# KASLI_CON.net
KiCad netlist of a schematic drawn in Altium Designer
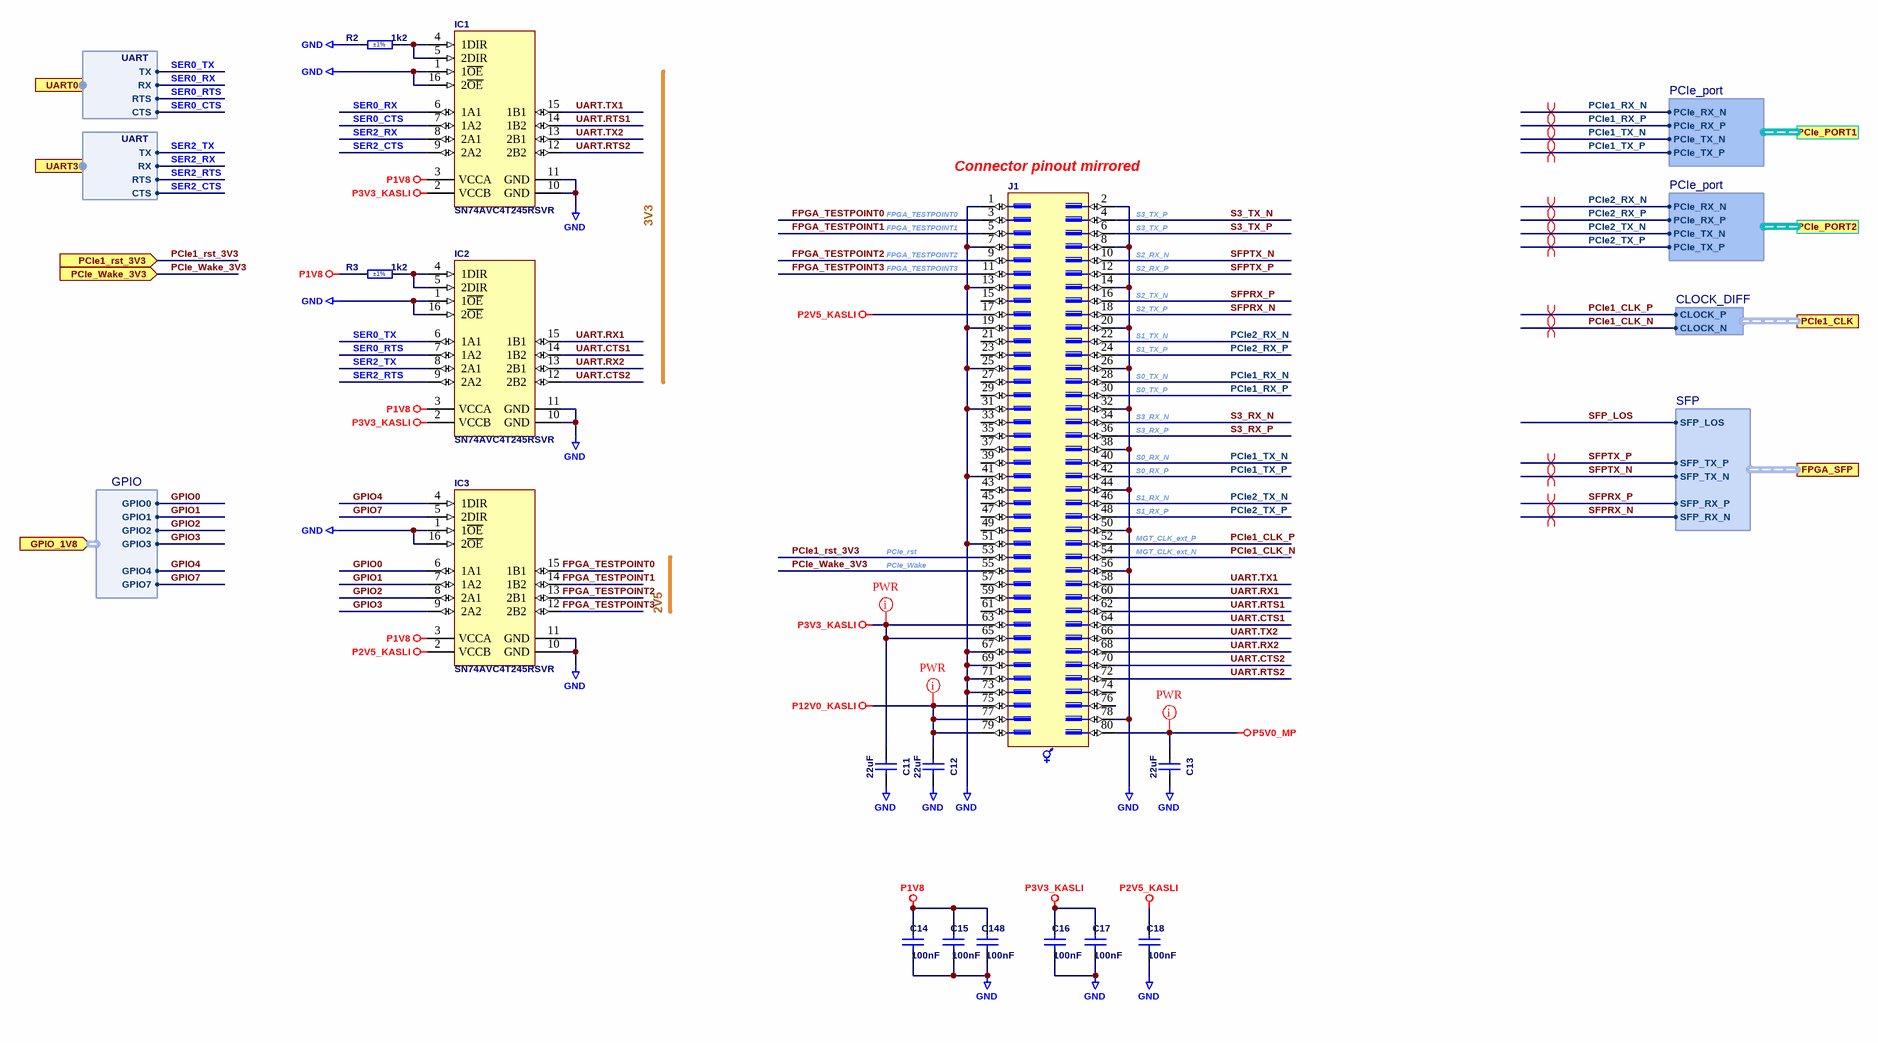
[diagram p0: KASLI_CON.SchDoc]

(export (version "E")
  (design (tool "Eeschema 10.0.6"))
  (components
    (comp (ref "C11")
      (value "22uF")
      (footprint "CAPC2012X135N")
      (description "Non-polarised capacitor")
      (fields
        (field (name "MANUFACTURER PART NUMBER") "CC0805_22UF_16V_10%_X5R")
        (field (name "MANUFACTURER") "GENERIC")
        (field (name "AUTHOR") "CERN DEM JLC")
      )
      (libsource (lib "Capacitors") (part "Capacitor - non polarized"))
    )
    (comp (ref "C12")
      (value "22uF")
      (footprint "CAPC2012X135N")
      (description "Non-polarised capacitor")
      (fields
        (field (name "MANUFACTURER PART NUMBER") "CC0805_22UF_16V_10%_X5R")
        (field (name "MANUFACTURER") "GENERIC")
        (field (name "AUTHOR") "CERN DEM JLC")
      )
      (libsource (lib "Capacitors") (part "Capacitor - non polarized"))
    )
    (comp (ref "C13")
      (value "22uF")
      (footprint "CAPC2012X135N")
      (description "Non-polarised capacitor")
      (fields
        (field (name "MANUFACTURER PART NUMBER") "CC0805_22UF_16V_10%_X5R")
        (field (name "MANUFACTURER") "GENERIC")
        (field (name "AUTHOR") "CERN DEM JLC")
      )
      (libsource (lib "Capacitors") (part "Capacitor - non polarized"))
    )
    (comp (ref "C14")
      (value "100nF")
      (footprint "CAPC1005X55N")
      (description "Non-polarised capacitor")
      (fields
        (field (name "PART NUMBER") "CC0402_100NF_16V_10%_X7R")
        (field (name "VOLTAGE") "16V")
        (field (name "AUTHOR") "CERN DEM JLC")
      )
      (libsource (lib "Capacitors") (part "Capacitor - non polarized"))
    )
    (comp (ref "C15")
      (value "100nF")
      (footprint "CAPC1005X55N")
      (description "Non-polarised capacitor")
      (fields
        (field (name "PART NUMBER") "CC0402_100NF_16V_10%_X7R")
        (field (name "VOLTAGE") "16V")
        (field (name "AUTHOR") "CERN DEM JLC")
      )
      (libsource (lib "Capacitors") (part "Capacitor - non polarized"))
    )
    (comp (ref "C16")
      (value "100nF")
      (footprint "CAPC1005X55N")
      (description "Non-polarised capacitor")
      (fields
        (field (name "PART NUMBER") "CC0402_100NF_16V_10%_X7R")
        (field (name "VOLTAGE") "16V")
        (field (name "AUTHOR") "CERN DEM JLC")
      )
      (libsource (lib "Capacitors") (part "Capacitor - non polarized"))
    )
    (comp (ref "C17")
      (value "100nF")
      (footprint "CAPC1005X55N")
      (description "Non-polarised capacitor")
      (fields
        (field (name "PART NUMBER") "CC0402_100NF_16V_10%_X7R")
        (field (name "VOLTAGE") "16V")
        (field (name "AUTHOR") "CERN DEM JLC")
      )
      (libsource (lib "Capacitors") (part "Capacitor - non polarized"))
    )
    (comp (ref "C18")
      (value "100nF")
      (footprint "CAPC1005X55N")
      (description "Non-polarised capacitor")
      (fields
        (field (name "PART NUMBER") "CC0402_100NF_16V_10%_X7R")
        (field (name "VOLTAGE") "16V")
        (field (name "AUTHOR") "CERN DEM JLC")
      )
      (libsource (lib "Capacitors") (part "Capacitor - non polarized"))
    )
    (comp (ref "C148")
      (value "100nF")
      (footprint "CAPC1005X55N")
      (description "Non-polarised capacitor")
      (fields
        (field (name "PART NUMBER") "CC0402_100NF_16V_10%_X7R")
        (field (name "VOLTAGE") "16V")
        (field (name "AUTHOR") "CERN DEM JLC")
      )
      (libsource (lib "Capacitors") (part "Capacitor - non polarized"))
    )
    (comp (ref "IC1")
      (value "SN74AVC4T245RSVR")
      (footprint "QFN40P180X260X55-16N")
      (description "4-Bit Dual-Supply Bus Transceiver with Configurable Voltage Translation and 3-State Output")
      (fields (field (name "MANUFACTURER") "TEXAS INSTRUMENTS") (field (name "AUTHOR") "CERN DEM JLC"))
      (libsource (lib "ICs And Semiconductors") (part "744T245_a"))
    )
    (comp (ref "IC2")
      (value "SN74AVC4T245RSVR")
      (footprint "QFN40P180X260X55-16N")
      (description "4-Bit Dual-Supply Bus Transceiver with Configurable Voltage Translation and 3-State Output")
      (fields (field (name "MANUFACTURER") "TEXAS INSTRUMENTS") (field (name "AUTHOR") "CERN DEM JLC"))
      (libsource (lib "ICs And Semiconductors") (part "744T245_a"))
    )
    (comp (ref "IC3")
      (value "SN74AVC4T245RSVR")
      (footprint "QFN40P180X260X55-16N")
      (description "4-Bit Dual-Supply Bus Transceiver with Configurable Voltage Translation and 3-State Output")
      (fields (field (name "MANUFACTURER") "TEXAS INSTRUMENTS") (field (name "AUTHOR") "CERN DEM JLC"))
      (libsource (lib "ICs And Semiconductors") (part "744T245_a"))
    )
    (comp (ref "J1")
      (value "~")
      (footprint "SAMTEC_LSS-140-01-L-DV-A")
      (description "Connector 80 Hermaphroditic")
      (fields
        (field (name "PART NUMBER") "SAMTEC_LSS-140-01-L-DV-A")
        (field (name "MANUFACTURER") "SAMTEC")
        (field (name "AUTHOR") "CERN DEM JMW")
      )
      (libsource (lib "Kasil_DIOT_x86_board") (part "SAMTEC_LSS-140-01-L-DV-A"))
    )
    (comp (ref "R2")
      (value "1k2")
      (footprint "RESC1005X40N")
      (description "Resistor - 1%")
      (fields
        (field (name "TOLERANCE") "±1%")
        (field (name "PART NUMBER") "R0402_1K2_1%_0.0625W_100PPM")
        (field (name "POWER") "0.0625W")
        (field (name "AUTHOR") "CERN DEM JLC")
      )
      (libsource (lib "Resistors") (part "Resistor - 1%"))
    )
    (comp (ref "R3")
      (value "1k2")
      (footprint "RESC1005X40N")
      (description "Resistor - 1%")
      (fields
        (field (name "TOLERANCE") "±1%")
        (field (name "PART NUMBER") "R0402_1K2_1%_0.0625W_100PPM")
        (field (name "POWER") "0.0625W")
        (field (name "AUTHOR") "CERN DEM JLC")
      )
      (libsource (lib "Resistors") (part "Resistor - 1%"))
    )
  )
  (nets
    (net (code "6") (name "/FPGA_TESTPOINT0") (class "Default")
      (node (ref "IC3") (pin "15") (pinfunction "1B1_15") (pintype "bidirectional"))
      (node (ref "J1") (pin "3") (pinfunction "3_3") (pintype "bidirectional"))
    )
    (net (code "7") (name "/FPGA_TESTPOINT1") (class "Default")
      (node (ref "IC3") (pin "14") (pinfunction "1B2_14") (pintype "bidirectional"))
      (node (ref "J1") (pin "5") (pinfunction "5_5") (pintype "bidirectional"))
    )
    (net (code "8") (name "/FPGA_TESTPOINT2") (class "Default")
      (node (ref "IC3") (pin "13") (pinfunction "2B1_13") (pintype "bidirectional"))
      (node (ref "J1") (pin "9") (pinfunction "9_9") (pintype "bidirectional"))
    )
    (net (code "9") (name "/FPGA_TESTPOINT3") (class "Default")
      (node (ref "IC3") (pin "12") (pinfunction "2B2_12") (pintype "bidirectional"))
      (node (ref "J1") (pin "11") (pinfunction "11_11") (pintype "bidirectional"))
    )
    (net (code "10") (name "/GPIO0") (class "Default")
      (node (ref "IC3") (pin "6") (pinfunction "1A1_6") (pintype "bidirectional"))
    )
    (net (code "11") (name "/GPIO1") (class "Default")
      (node (ref "IC3") (pin "7") (pinfunction "1A2_7") (pintype "bidirectional"))
    )
    (net (code "12") (name "/GPIO2") (class "Default")
      (node (ref "IC3") (pin "8") (pinfunction "2A1_8") (pintype "bidirectional"))
    )
    (net (code "13") (name "/GPIO3") (class "Default")
      (node (ref "IC3") (pin "9") (pinfunction "2A2_9") (pintype "bidirectional"))
    )
    (net (code "14") (name "/GPIO4") (class "Default")
      (node (ref "IC3") (pin "4") (pinfunction "1DIR_4") (pintype "input"))
    )
    (net (code "15") (name "/GPIO7") (class "Default")
      (node (ref "IC3") (pin "5") (pinfunction "2DIR_5") (pintype "input"))
    )
    (net (code "16") (name "/PCIe1_CLK_N") (class "Default")
      (node (ref "J1") (pin "54") (pinfunction "54_54") (pintype "bidirectional"))
    )
    (net (code "17") (name "/PCIe1_CLK_P") (class "Default")
      (node (ref "J1") (pin "52") (pinfunction "52_52") (pintype "bidirectional"))
    )
    (net (code "18") (name "/PCIe1_RX_N") (class "Default")
      (node (ref "J1") (pin "28") (pinfunction "28_28") (pintype "bidirectional"))
    )
    (net (code "19") (name "/PCIe1_RX_P") (class "Default")
      (node (ref "J1") (pin "30") (pinfunction "30_30") (pintype "bidirectional"))
    )
    (net (code "20") (name "/PCIe1_TX_N") (class "Default")
      (node (ref "J1") (pin "40") (pinfunction "40_40") (pintype "bidirectional"))
    )
    (net (code "21") (name "/PCIe1_TX_P") (class "Default")
      (node (ref "J1") (pin "42") (pinfunction "42_42") (pintype "bidirectional"))
    )
    (net (code "22") (name "/PCIe1_rst_3V3") (class "Default")
      (node (ref "J1") (pin "53") (pinfunction "53_53") (pintype "bidirectional"))
    )
    (net (code "23") (name "/PCIe2_RX_N") (class "Default")
      (node (ref "J1") (pin "22") (pinfunction "22_22") (pintype "bidirectional"))
    )
    (net (code "24") (name "/PCIe2_RX_P") (class "Default")
      (node (ref "J1") (pin "24") (pinfunction "24_24") (pintype "bidirectional"))
    )
    (net (code "25") (name "/PCIe2_TX_N") (class "Default")
      (node (ref "J1") (pin "46") (pinfunction "46_46") (pintype "bidirectional"))
    )
    (net (code "26") (name "/PCIe2_TX_P") (class "Default")
      (node (ref "J1") (pin "48") (pinfunction "48_48") (pintype "bidirectional"))
    )
    (net (code "27") (name "/PCIe_Wake_3V3") (class "Default")
      (node (ref "J1") (pin "55") (pinfunction "55_55") (pintype "bidirectional"))
    )
    (net (code "28") (name "/S3_RX_N") (class "Default")
      (node (ref "J1") (pin "34") (pinfunction "34_34") (pintype "bidirectional"))
    )
    (net (code "29") (name "/S3_RX_P") (class "Default")
      (node (ref "J1") (pin "36") (pinfunction "36_36") (pintype "bidirectional"))
    )
    (net (code "30") (name "/S3_TX_N") (class "Default")
      (node (ref "J1") (pin "4") (pinfunction "4_4") (pintype "bidirectional"))
    )
    (net (code "31") (name "/S3_TX_P") (class "Default")
      (node (ref "J1") (pin "6") (pinfunction "6_6") (pintype "bidirectional"))
    )
    (net (code "32") (name "/SER0_CTS") (class "Default")
      (node (ref "IC1") (pin "7") (pinfunction "1A2_7") (pintype "bidirectional"))
    )
    (net (code "33") (name "/SER0_RTS") (class "Default")
      (node (ref "IC2") (pin "7") (pinfunction "1A2_7") (pintype "bidirectional"))
    )
    (net (code "34") (name "/SER0_RX") (class "Default")
      (node (ref "IC1") (pin "6") (pinfunction "1A1_6") (pintype "bidirectional"))
    )
    (net (code "35") (name "/SER0_TX") (class "Default")
      (node (ref "IC2") (pin "6") (pinfunction "1A1_6") (pintype "bidirectional"))
    )
    (net (code "36") (name "/SER2_CTS") (class "Default")
      (node (ref "IC1") (pin "9") (pinfunction "2A2_9") (pintype "bidirectional"))
    )
    (net (code "37") (name "/SER2_RTS") (class "Default")
      (node (ref "IC2") (pin "9") (pinfunction "2A2_9") (pintype "bidirectional"))
    )
    (net (code "38") (name "/SER2_RX") (class "Default")
      (node (ref "IC1") (pin "8") (pinfunction "2A1_8") (pintype "bidirectional"))
    )
    (net (code "39") (name "/SER2_TX") (class "Default")
      (node (ref "IC2") (pin "8") (pinfunction "2A1_8") (pintype "bidirectional"))
    )
    (net (code "40") (name "/SFPRX_N") (class "Default")
      (node (ref "J1") (pin "18") (pinfunction "18_18") (pintype "bidirectional"))
    )
    (net (code "41") (name "/SFPRX_P") (class "Default")
      (node (ref "J1") (pin "16") (pinfunction "16_16") (pintype "bidirectional"))
    )
    (net (code "42") (name "/SFPTX_N") (class "Default")
      (node (ref "J1") (pin "10") (pinfunction "10_10") (pintype "bidirectional"))
    )
    (net (code "43") (name "/SFPTX_P") (class "Default")
      (node (ref "J1") (pin "12") (pinfunction "12_12") (pintype "bidirectional"))
    )
    (net (code "45") (name "/UART.CTS1") (class "Default")
      (node (ref "IC2") (pin "14") (pinfunction "1B2_14") (pintype "bidirectional"))
      (node (ref "J1") (pin "64") (pinfunction "64_64") (pintype "bidirectional"))
    )
    (net (code "46") (name "/UART.CTS2") (class "Default")
      (node (ref "IC2") (pin "12") (pinfunction "2B2_12") (pintype "bidirectional"))
      (node (ref "J1") (pin "70") (pinfunction "70_70") (pintype "bidirectional"))
    )
    (net (code "47") (name "/UART.RTS1") (class "Default")
      (node (ref "IC1") (pin "14") (pinfunction "1B2_14") (pintype "bidirectional"))
      (node (ref "J1") (pin "62") (pinfunction "62_62") (pintype "bidirectional"))
    )
    (net (code "48") (name "/UART.RTS2") (class "Default")
      (node (ref "IC1") (pin "12") (pinfunction "2B2_12") (pintype "bidirectional"))
      (node (ref "J1") (pin "72") (pinfunction "72_72") (pintype "bidirectional"))
    )
    (net (code "49") (name "/UART.RX1") (class "Default")
      (node (ref "IC2") (pin "15") (pinfunction "1B1_15") (pintype "bidirectional"))
      (node (ref "J1") (pin "60") (pinfunction "60_60") (pintype "bidirectional"))
    )
    (net (code "50") (name "/UART.RX2") (class "Default")
      (node (ref "IC2") (pin "13") (pinfunction "2B1_13") (pintype "bidirectional"))
      (node (ref "J1") (pin "68") (pinfunction "68_68") (pintype "bidirectional"))
    )
    (net (code "51") (name "/UART.TX1") (class "Default")
      (node (ref "IC1") (pin "15") (pinfunction "1B1_15") (pintype "bidirectional"))
      (node (ref "J1") (pin "58") (pinfunction "58_58") (pintype "bidirectional"))
    )
    (net (code "52") (name "/UART.TX2") (class "Default")
      (node (ref "IC1") (pin "13") (pinfunction "2B1_13") (pintype "bidirectional"))
      (node (ref "J1") (pin "66") (pinfunction "66_66") (pintype "bidirectional"))
    )
    (net (code "58") (name "GND") (class "Default")
      (node (ref "C11") (pin "1") (pinfunction "1_1") (pintype "passive"))
      (node (ref "C12") (pin "1") (pinfunction "1_1") (pintype "passive"))
      (node (ref "C13") (pin "1") (pinfunction "1_1") (pintype "passive"))
      (node (ref "C14") (pin "1") (pinfunction "1_1") (pintype "passive"))
      (node (ref "C148") (pin "1") (pinfunction "1_1") (pintype "passive"))
      (node (ref "C15") (pin "1") (pinfunction "1_1") (pintype "passive"))
      (node (ref "C16") (pin "1") (pinfunction "1_1") (pintype "passive"))
      (node (ref "C17") (pin "1") (pinfunction "1_1") (pintype "passive"))
      (node (ref "C18") (pin "1") (pinfunction "1_1") (pintype "passive"))
      (node (ref "IC1") (pin "1") (pinfunction "1~{OE}_1") (pintype "input"))
      (node (ref "IC1") (pin "10") (pinfunction "GND_10") (pintype "power_in"))
      (node (ref "IC1") (pin "11") (pinfunction "GND_11") (pintype "power_in"))
      (node (ref "IC1") (pin "16") (pinfunction "2~{OE}_16") (pintype "input"))
      (node (ref "IC2") (pin "1") (pinfunction "1~{OE}_1") (pintype "input"))
      (node (ref "IC2") (pin "10") (pinfunction "GND_10") (pintype "power_in"))
      (node (ref "IC2") (pin "11") (pinfunction "GND_11") (pintype "power_in"))
      (node (ref "IC2") (pin "16") (pinfunction "2~{OE}_16") (pintype "input"))
      (node (ref "IC3") (pin "1") (pinfunction "1~{OE}_1") (pintype "input"))
      (node (ref "IC3") (pin "10") (pinfunction "GND_10") (pintype "power_in"))
      (node (ref "IC3") (pin "11") (pinfunction "GND_11") (pintype "power_in"))
      (node (ref "IC3") (pin "16") (pinfunction "2~{OE}_16") (pintype "input"))
      (node (ref "J1") (pin "1") (pinfunction "1_1") (pintype "bidirectional"))
      (node (ref "J1") (pin "13") (pinfunction "13_13") (pintype "bidirectional"))
      (node (ref "J1") (pin "14") (pinfunction "14_14") (pintype "bidirectional"))
      (node (ref "J1") (pin "19") (pinfunction "19_19") (pintype "bidirectional"))
      (node (ref "J1") (pin "2") (pinfunction "2_2") (pintype "bidirectional"))
      (node (ref "J1") (pin "20") (pinfunction "20_20") (pintype "bidirectional"))
      (node (ref "J1") (pin "25") (pinfunction "25_25") (pintype "bidirectional"))
      (node (ref "J1") (pin "26") (pinfunction "26_26") (pintype "bidirectional"))
      (node (ref "J1") (pin "31") (pinfunction "31_31") (pintype "bidirectional"))
      (node (ref "J1") (pin "32") (pinfunction "32_32") (pintype "bidirectional"))
      (node (ref "J1") (pin "38") (pinfunction "38_38") (pintype "bidirectional"))
      (node (ref "J1") (pin "41") (pinfunction "41_41") (pintype "bidirectional"))
      (node (ref "J1") (pin "44") (pinfunction "44_44") (pintype "bidirectional"))
      (node (ref "J1") (pin "50") (pinfunction "50_50") (pintype "bidirectional"))
      (node (ref "J1") (pin "51") (pinfunction "51_51") (pintype "bidirectional"))
      (node (ref "J1") (pin "56") (pinfunction "56_56") (pintype "bidirectional"))
      (node (ref "J1") (pin "67") (pinfunction "67_67") (pintype "bidirectional"))
      (node (ref "J1") (pin "69") (pinfunction "69_69") (pintype "bidirectional"))
      (node (ref "J1") (pin "7") (pinfunction "7_7") (pintype "bidirectional"))
      (node (ref "J1") (pin "71") (pinfunction "71_71") (pintype "bidirectional"))
      (node (ref "J1") (pin "73") (pinfunction "73_73") (pintype "bidirectional"))
      (node (ref "J1") (pin "78") (pinfunction "78_78") (pintype "bidirectional"))
      (node (ref "J1") (pin "8") (pinfunction "8_8") (pintype "bidirectional"))
      (node (ref "R2") (pin "1") (pinfunction "1_1") (pintype "passive"))
    )
    (net (code "59") (name "Net-(IC1-1DIR)") (class "Default")
      (node (ref "IC1") (pin "4") (pinfunction "1DIR_4") (pintype "input"))
      (node (ref "IC1") (pin "5") (pinfunction "2DIR_5") (pintype "input"))
      (node (ref "R2") (pin "2") (pinfunction "2_2") (pintype "passive"))
    )
    (net (code "60") (name "Net-(IC2-1DIR)") (class "Default")
      (node (ref "IC2") (pin "4") (pinfunction "1DIR_4") (pintype "input"))
      (node (ref "IC2") (pin "5") (pinfunction "2DIR_5") (pintype "input"))
      (node (ref "R3") (pin "2") (pinfunction "2_2") (pintype "passive"))
    )
    (net (code "61") (name "P1V8") (class "Default")
      (node (ref "C14") (pin "2") (pinfunction "2_2") (pintype "passive"))
      (node (ref "C148") (pin "2") (pinfunction "2_2") (pintype "passive"))
      (node (ref "C15") (pin "2") (pinfunction "2_2") (pintype "passive"))
      (node (ref "IC1") (pin "3") (pinfunction "VCCA_3") (pintype "power_in"))
      (node (ref "IC2") (pin "3") (pinfunction "VCCA_3") (pintype "power_in"))
      (node (ref "IC3") (pin "3") (pinfunction "VCCA_3") (pintype "power_in"))
      (node (ref "R3") (pin "1") (pinfunction "1_1") (pintype "passive"))
    )
    (net (code "62") (name "P2V5_KASLI") (class "Default")
      (node (ref "C18") (pin "2") (pinfunction "2_2") (pintype "passive"))
      (node (ref "IC3") (pin "2") (pinfunction "VCCB_2") (pintype "power_in"))
      (node (ref "J1") (pin "17") (pinfunction "17_17") (pintype "bidirectional"))
    )
    (net (code "63") (name "P3V3_KASLI") (class "Default")
      (node (ref "C11") (pin "2") (pinfunction "2_2") (pintype "passive"))
      (node (ref "C16") (pin "2") (pinfunction "2_2") (pintype "passive"))
      (node (ref "C17") (pin "2") (pinfunction "2_2") (pintype "passive"))
      (node (ref "IC1") (pin "2") (pinfunction "VCCB_2") (pintype "power_in"))
      (node (ref "IC2") (pin "2") (pinfunction "VCCB_2") (pintype "power_in"))
      (node (ref "J1") (pin "63") (pinfunction "63_63") (pintype "bidirectional"))
      (node (ref "J1") (pin "65") (pinfunction "65_65") (pintype "bidirectional"))
    )
    (net (code "64") (name "P5V0_MP") (class "Default")
      (node (ref "C13") (pin "2") (pinfunction "2_2") (pintype "passive"))
      (node (ref "J1") (pin "80") (pinfunction "80_80") (pintype "bidirectional"))
    )
    (net (code "65") (name "P12V0_KASLI") (class "Default")
      (node (ref "C12") (pin "2") (pinfunction "2_2") (pintype "passive"))
      (node (ref "J1") (pin "75") (pinfunction "75_75") (pintype "bidirectional"))
      (node (ref "J1") (pin "77") (pinfunction "77_77") (pintype "bidirectional"))
      (node (ref "J1") (pin "79") (pinfunction "79_79") (pintype "bidirectional"))
    )
    (net (code "66") (name "unconnected-(J1-Pad15)") (class "Default")
      (node (ref "J1") (pin "15") (pinfunction "15_15") (pintype "bidirectional"))
    )
    (net (code "67") (name "unconnected-(J1-Pad21)") (class "Default")
      (node (ref "J1") (pin "21") (pinfunction "21_21") (pintype "bidirectional"))
    )
    (net (code "68") (name "unconnected-(J1-Pad23)") (class "Default")
      (node (ref "J1") (pin "23") (pinfunction "23_23") (pintype "bidirectional"))
    )
    (net (code "69") (name "unconnected-(J1-Pad27)") (class "Default")
      (node (ref "J1") (pin "27") (pinfunction "27_27") (pintype "bidirectional"))
    )
    (net (code "70") (name "unconnected-(J1-Pad29)") (class "Default")
      (node (ref "J1") (pin "29") (pinfunction "29_29") (pintype "bidirectional"))
    )
    (net (code "71") (name "unconnected-(J1-Pad33)") (class "Default")
      (node (ref "J1") (pin "33") (pinfunction "33_33") (pintype "bidirectional"))
    )
    (net (code "72") (name "unconnected-(J1-Pad35)") (class "Default")
      (node (ref "J1") (pin "35") (pinfunction "35_35") (pintype "bidirectional"))
    )
    (net (code "73") (name "unconnected-(J1-Pad37)") (class "Default")
      (node (ref "J1") (pin "37") (pinfunction "37_37") (pintype "bidirectional"))
    )
    (net (code "74") (name "unconnected-(J1-Pad39)") (class "Default")
      (node (ref "J1") (pin "39") (pinfunction "39_39") (pintype "bidirectional"))
    )
    (net (code "75") (name "unconnected-(J1-Pad43)") (class "Default")
      (node (ref "J1") (pin "43") (pinfunction "43_43") (pintype "bidirectional"))
    )
    (net (code "76") (name "unconnected-(J1-Pad45)") (class "Default")
      (node (ref "J1") (pin "45") (pinfunction "45_45") (pintype "bidirectional"))
    )
    (net (code "77") (name "unconnected-(J1-Pad47)") (class "Default")
      (node (ref "J1") (pin "47") (pinfunction "47_47") (pintype "bidirectional"))
    )
    (net (code "78") (name "unconnected-(J1-Pad49)") (class "Default")
      (node (ref "J1") (pin "49") (pinfunction "49_49") (pintype "bidirectional"))
    )
    (net (code "79") (name "unconnected-(J1-Pad57)") (class "Default")
      (node (ref "J1") (pin "57") (pinfunction "57_57") (pintype "bidirectional"))
    )
    (net (code "80") (name "unconnected-(J1-Pad59)") (class "Default")
      (node (ref "J1") (pin "59") (pinfunction "59_59") (pintype "bidirectional"))
    )
    (net (code "81") (name "unconnected-(J1-Pad61)") (class "Default")
      (node (ref "J1") (pin "61") (pinfunction "61_61") (pintype "bidirectional"))
    )
    (net (code "82") (name "unconnected-(J1-Pad74)") (class "Default")
      (node (ref "J1") (pin "74") (pinfunction "74_74") (pintype "bidirectional"))
    )
    (net (code "83") (name "unconnected-(J1-Pad76)") (class "Default")
      (node (ref "J1") (pin "76") (pinfunction "76_76") (pintype "bidirectional"))
    )
  )
)
